# Voltage-Monitor.net
KiCad netlist of a schematic drawn in Altium Designer
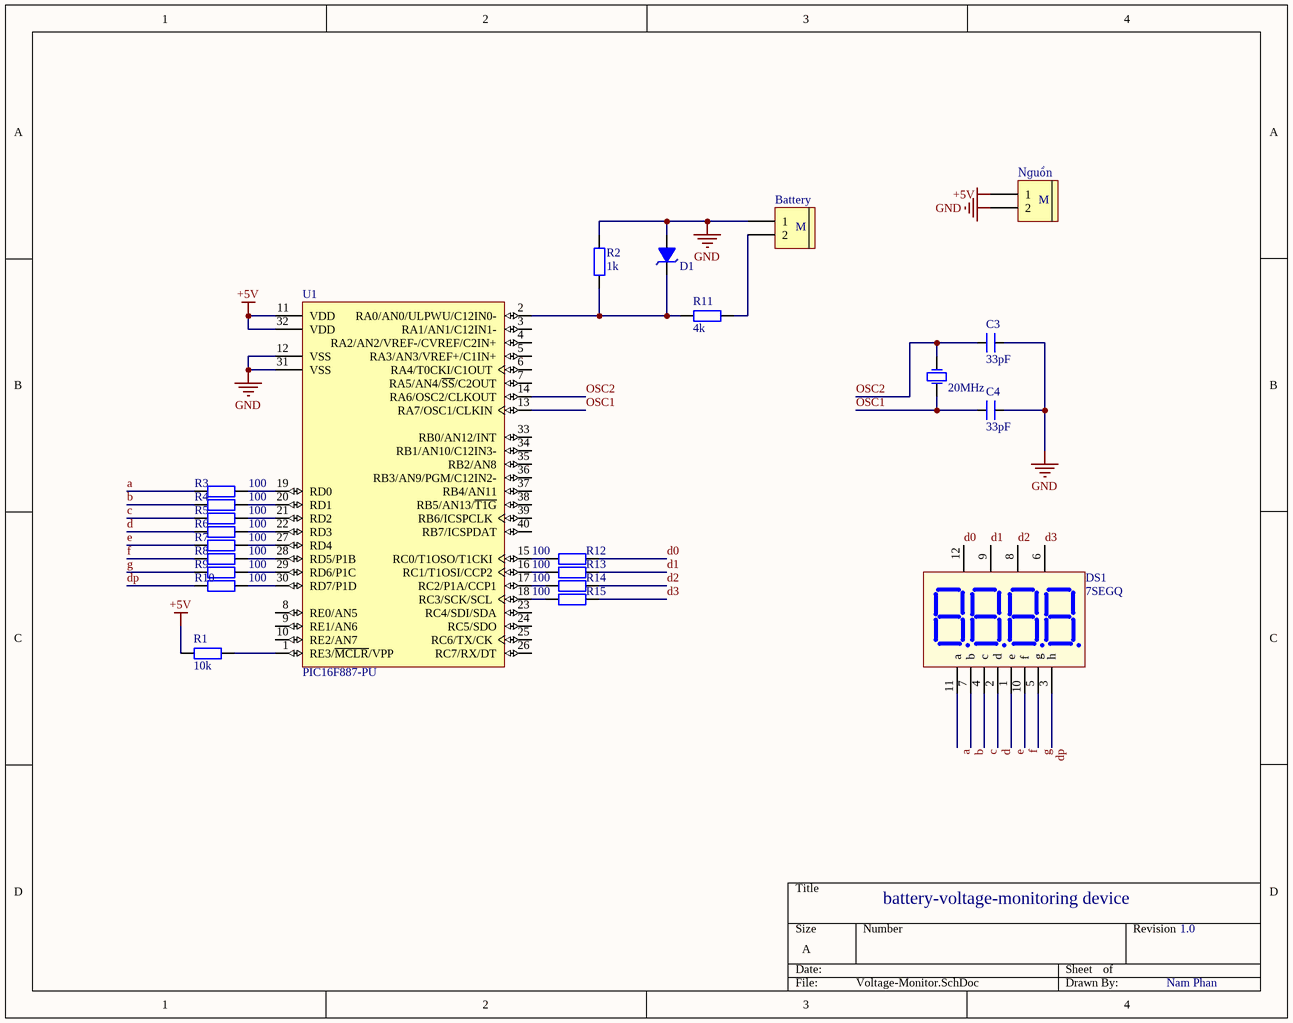
[diagram p0: Voltage-Monitor.SchDoc]

(export (version "E")
  (design (tool "Eeschema 10.0.6"))
  (components
    (comp (ref "Battery")
      (value "Header 2 - M")
      (footprint "Medium - Header 2")
      (description "Header, 2-Pin, Medium")
      (fields (field (name "PUBLISHER") "Altium Limited"))
      (libsource (lib "minhha") (part "Header 2 - M"))
    )
    (comp (ref "C3")
      (value "33pF")
      (footprint "CN1.5")
      (description "Cap np 682pF => 104pF")
      (libsource (lib "minhha") (part "CN1.5"))
    )
    (comp (ref "C4")
      (value "33pF")
      (footprint "CN1.5")
      (description "Cap np 682pF => 104pF")
      (libsource (lib "minhha") (part "CN1.5"))
    )
    (comp (ref "D1")
      (value "Diode Zener")
      (footprint "D1A")
      (description "Diode  Zener")
      (libsource (lib "minhha") (part "Diode Zener"))
    )
    (comp (ref "DS1")
      (value "7SEGQ")
      (footprint "LED7SEG-4-0.56")
      (description "Four 7 Seg Dipslay")
      (libsource (lib "Library1") (part "LED7SEG-4"))
    )
    (comp (ref "Nguồn")
      (value "Header 2 - M")
      (footprint "Medium - Header 2")
      (description "Header, 2-Pin, Medium")
      (fields (field (name "PUBLISHER") "Altium Limited"))
      (libsource (lib "minhha") (part "Header 2 - M"))
    )
    (comp (ref "R1")
      (value "10k")
      (footprint "R1/4W")
      (description "Resistor 1/4W")
      (libsource (lib "minhha") (part "R1/4W"))
    )
    (comp (ref "R2")
      (value "1k")
      (footprint "R1/4W")
      (description "Resistor 1/4W")
      (libsource (lib "minhha") (part "R1/4W"))
    )
    (comp (ref "R3")
      (value "100")
      (footprint "RESC-0603 (1608)")
      (description "RES SMD 5.6K OHM 1% 1/10W 0603")
      (fields (field (name "MPN") "RC0603FR-075K6L"))
      (libsource (lib "BYTECH_HW_LIB_2019 (1)") (part "RC0603FR-075K6L"))
    )
    (comp (ref "R4")
      (value "100")
      (footprint "RESC-0603 (1608)")
      (description "RES SMD 5.6K OHM 1% 1/10W 0603")
      (fields (field (name "MPN") "RC0603FR-075K6L"))
      (libsource (lib "BYTECH_HW_LIB_2019 (1)") (part "RC0603FR-075K6L"))
    )
    (comp (ref "R5")
      (value "100")
      (footprint "RESC-0603 (1608)")
      (description "RES SMD 5.6K OHM 1% 1/10W 0603")
      (fields (field (name "MPN") "RC0603FR-075K6L"))
      (libsource (lib "BYTECH_HW_LIB_2019 (1)") (part "RC0603FR-075K6L"))
    )
    (comp (ref "R6")
      (value "100")
      (footprint "RESC-0603 (1608)")
      (description "RES SMD 5.6K OHM 1% 1/10W 0603")
      (fields (field (name "MPN") "RC0603FR-075K6L"))
      (libsource (lib "BYTECH_HW_LIB_2019 (1)") (part "RC0603FR-075K6L"))
    )
    (comp (ref "R7")
      (value "100")
      (footprint "RESC-0603 (1608)")
      (description "RES SMD 5.6K OHM 1% 1/10W 0603")
      (fields (field (name "MPN") "RC0603FR-075K6L"))
      (libsource (lib "BYTECH_HW_LIB_2019 (1)") (part "RC0603FR-075K6L"))
    )
    (comp (ref "R8")
      (value "100")
      (footprint "RESC-0603 (1608)")
      (description "RES SMD 5.6K OHM 1% 1/10W 0603")
      (fields (field (name "MPN") "RC0603FR-075K6L"))
      (libsource (lib "BYTECH_HW_LIB_2019 (1)") (part "RC0603FR-075K6L"))
    )
    (comp (ref "R9")
      (value "100")
      (footprint "RESC-0603 (1608)")
      (description "RES SMD 5.6K OHM 1% 1/10W 0603")
      (fields (field (name "MPN") "RC0603FR-075K6L"))
      (libsource (lib "BYTECH_HW_LIB_2019 (1)") (part "RC0603FR-075K6L"))
    )
    (comp (ref "R10")
      (value "100")
      (footprint "RESC-0603 (1608)")
      (description "RES SMD 5.6K OHM 1% 1/10W 0603")
      (fields (field (name "MPN") "RC0603FR-075K6L"))
      (libsource (lib "BYTECH_HW_LIB_2019 (1)") (part "RC0603FR-075K6L"))
    )
    (comp (ref "R11")
      (value "4k")
      (footprint "R1/4W")
      (description "Resistor 1/4W")
      (libsource (lib "minhha") (part "R1/4W"))
    )
    (comp (ref "R12")
      (value "100")
      (footprint "RESC-0603 (1608)")
      (description "RES SMD 5.6K OHM 1% 1/10W 0603")
      (fields (field (name "MPN") "RC0603FR-075K6L"))
      (libsource (lib "BYTECH_HW_LIB_2019 (1)") (part "RC0603FR-075K6L"))
    )
    (comp (ref "R13")
      (value "100")
      (footprint "RESC-0603 (1608)")
      (description "RES SMD 5.6K OHM 1% 1/10W 0603")
      (fields (field (name "MPN") "RC0603FR-075K6L"))
      (libsource (lib "BYTECH_HW_LIB_2019 (1)") (part "RC0603FR-075K6L"))
    )
    (comp (ref "R14")
      (value "100")
      (footprint "RESC-0603 (1608)")
      (description "RES SMD 5.6K OHM 1% 1/10W 0603")
      (fields (field (name "MPN") "RC0603FR-075K6L"))
      (libsource (lib "BYTECH_HW_LIB_2019 (1)") (part "RC0603FR-075K6L"))
    )
    (comp (ref "R15")
      (value "100")
      (footprint "RESC-0603 (1608)")
      (description "RES SMD 5.6K OHM 1% 1/10W 0603")
      (fields (field (name "MPN") "RC0603FR-075K6L"))
      (libsource (lib "BYTECH_HW_LIB_2019 (1)") (part "RC0603FR-075K6L"))
    )
    (comp (ref "U1")
      (value "PIC16F887-PU")
      (footprint "DIP40/W0.6")
      (fields (field (name "PUBLISHER") "Altium Limited"))
      (libsource (lib "Library1") (part "PIC16F887-PU"))
    )
    (comp (ref "Y1")
      (value "20MHz")
      (footprint "XT2")
      (description "Crystal Oscillator")
      (fields (field (name "PUBLISHER") "Altium Limited"))
      (libsource (lib "minhha") (part "Crystal"))
    )
  )
  (nets
    (net (code "1") (name "+5V") (class "Default")
      (node (ref "Nguồn") (pin "1") (pinfunction "1_1") (pintype "passive"))
      (node (ref "R1") (pin "1") (pinfunction "1_1") (pintype "passive"))
      (node (ref "U1") (pin "11") (pinfunction "VDD_11") (pintype "power_in"))
      (node (ref "U1") (pin "32") (pinfunction "VDD_32") (pintype "power_in"))
    )
    (net (code "2") (name "/OSC1") (class "Default")
      (node (ref "C4") (pin "1") (pinfunction "1_1") (pintype "passive"))
      (node (ref "U1") (pin "13") (pinfunction "RA7/OSC1/CLKIN_13") (pintype "bidirectional"))
      (node (ref "Y1") (pin "1") (pinfunction "OSC1_1") (pintype "passive"))
    )
    (net (code "3") (name "/OSC2") (class "Default")
      (node (ref "C3") (pin "1") (pinfunction "1_1") (pintype "passive"))
      (node (ref "U1") (pin "14") (pinfunction "RA6/OSC2/CLKOUT_14") (pintype "bidirectional"))
      (node (ref "Y1") (pin "2") (pinfunction "OSC2_2") (pintype "passive"))
    )
    (net (code "4") (name "/a") (class "Default")
      (node (ref "DS1") (pin "11") (pinfunction "a_11") (pintype "passive"))
      (node (ref "R3") (pin "1") (pinfunction "1_1") (pintype "passive"))
    )
    (net (code "5") (name "/b") (class "Default")
      (node (ref "DS1") (pin "7") (pinfunction "b_7") (pintype "passive"))
      (node (ref "R4") (pin "1") (pinfunction "1_1") (pintype "passive"))
    )
    (net (code "6") (name "/c") (class "Default")
      (node (ref "DS1") (pin "4") (pinfunction "c_4") (pintype "passive"))
      (node (ref "R5") (pin "1") (pinfunction "1_1") (pintype "passive"))
    )
    (net (code "7") (name "/d") (class "Default")
      (node (ref "DS1") (pin "2") (pinfunction "d_2") (pintype "passive"))
      (node (ref "R6") (pin "1") (pinfunction "1_1") (pintype "passive"))
    )
    (net (code "8") (name "/d0") (class "Default")
      (node (ref "DS1") (pin "12") (pinfunction "V1_12") (pintype "passive"))
      (node (ref "R12") (pin "2") (pinfunction "2_2") (pintype "passive"))
    )
    (net (code "9") (name "/d1") (class "Default")
      (node (ref "DS1") (pin "9") (pinfunction "V2_9") (pintype "passive"))
      (node (ref "R13") (pin "2") (pinfunction "2_2") (pintype "passive"))
    )
    (net (code "10") (name "/d2") (class "Default")
      (node (ref "DS1") (pin "8") (pinfunction "V3_8") (pintype "passive"))
      (node (ref "R14") (pin "2") (pinfunction "2_2") (pintype "passive"))
    )
    (net (code "11") (name "/d3") (class "Default")
      (node (ref "DS1") (pin "6") (pinfunction "V4_6") (pintype "passive"))
      (node (ref "R15") (pin "2") (pinfunction "2_2") (pintype "passive"))
    )
    (net (code "12") (name "/dp") (class "Default")
      (node (ref "DS1") (pin "3") (pinfunction "h_3") (pintype "passive"))
      (node (ref "R10") (pin "1") (pinfunction "1_1") (pintype "passive"))
    )
    (net (code "13") (name "/e") (class "Default")
      (node (ref "DS1") (pin "1") (pinfunction "e_1") (pintype "passive"))
      (node (ref "R7") (pin "1") (pinfunction "1_1") (pintype "passive"))
    )
    (net (code "14") (name "/f") (class "Default")
      (node (ref "DS1") (pin "10") (pinfunction "f_10") (pintype "passive"))
      (node (ref "R8") (pin "1") (pinfunction "1_1") (pintype "passive"))
    )
    (net (code "15") (name "/g") (class "Default")
      (node (ref "DS1") (pin "5") (pinfunction "g_5") (pintype "passive"))
      (node (ref "R9") (pin "1") (pinfunction "1_1") (pintype "passive"))
    )
    (net (code "16") (name "GND") (class "Default")
      (node (ref "Battery") (pin "1") (pinfunction "1_1") (pintype "passive"))
      (node (ref "C3") (pin "2") (pinfunction "2_2") (pintype "passive"))
      (node (ref "C4") (pin "2") (pinfunction "2_2") (pintype "passive"))
      (node (ref "D1") (pin "1") (pinfunction "A_1") (pintype "passive"))
      (node (ref "Nguồn") (pin "2") (pinfunction "2_2") (pintype "passive"))
      (node (ref "R2") (pin "2") (pinfunction "2_2") (pintype "passive"))
      (node (ref "U1") (pin "12") (pinfunction "VSS_12") (pintype "power_in"))
      (node (ref "U1") (pin "31") (pinfunction "VSS_31") (pintype "power_in"))
    )
    (net (code "17") (name "Net-(Battery-Pad2)") (class "Default")
      (node (ref "Battery") (pin "2") (pinfunction "2_2") (pintype "passive"))
      (node (ref "R11") (pin "2") (pinfunction "2_2") (pintype "passive"))
    )
    (net (code "18") (name "Net-(D1-K)") (class "Default")
      (node (ref "D1") (pin "2") (pinfunction "K_2") (pintype "passive"))
      (node (ref "R11") (pin "1") (pinfunction "1_1") (pintype "passive"))
      (node (ref "R2") (pin "1") (pinfunction "1_1") (pintype "passive"))
      (node (ref "U1") (pin "2") (pinfunction "RA0/AN0/ULPWU/C12IN0-_2") (pintype "bidirectional"))
    )
    (net (code "19") (name "Net-(U1-RC0{slash}T1OSO{slash}T1CKI)") (class "Default")
      (node (ref "R12") (pin "1") (pinfunction "1_1") (pintype "passive"))
      (node (ref "U1") (pin "15") (pinfunction "RC0/T1OSO/T1CKI_15") (pintype "bidirectional"))
    )
    (net (code "20") (name "Net-(U1-RC1{slash}T1OSI{slash}CCP2)") (class "Default")
      (node (ref "R13") (pin "1") (pinfunction "1_1") (pintype "passive"))
      (node (ref "U1") (pin "16") (pinfunction "RC1/T1OSI/CCP2_16") (pintype "bidirectional"))
    )
    (net (code "21") (name "Net-(U1-RC2{slash}P1A{slash}CCP1)") (class "Default")
      (node (ref "R14") (pin "1") (pinfunction "1_1") (pintype "passive"))
      (node (ref "U1") (pin "17") (pinfunction "RC2/P1A/CCP1_17") (pintype "bidirectional"))
    )
    (net (code "22") (name "Net-(U1-RC3{slash}SCK{slash}SCL)") (class "Default")
      (node (ref "R15") (pin "1") (pinfunction "1_1") (pintype "passive"))
      (node (ref "U1") (pin "18") (pinfunction "RC3/SCK/SCL_18") (pintype "bidirectional"))
    )
    (net (code "23") (name "Net-(U1-RD0)") (class "Default")
      (node (ref "R3") (pin "2") (pinfunction "2_2") (pintype "passive"))
      (node (ref "U1") (pin "19") (pinfunction "RD0_19") (pintype "bidirectional"))
    )
    (net (code "24") (name "Net-(U1-RD1)") (class "Default")
      (node (ref "R4") (pin "2") (pinfunction "2_2") (pintype "passive"))
      (node (ref "U1") (pin "20") (pinfunction "RD1_20") (pintype "bidirectional"))
    )
    (net (code "25") (name "Net-(U1-RD2)") (class "Default")
      (node (ref "R5") (pin "2") (pinfunction "2_2") (pintype "passive"))
      (node (ref "U1") (pin "21") (pinfunction "RD2_21") (pintype "bidirectional"))
    )
    (net (code "26") (name "Net-(U1-RD3)") (class "Default")
      (node (ref "R6") (pin "2") (pinfunction "2_2") (pintype "passive"))
      (node (ref "U1") (pin "22") (pinfunction "RD3_22") (pintype "bidirectional"))
    )
    (net (code "27") (name "Net-(U1-RD4)") (class "Default")
      (node (ref "R7") (pin "2") (pinfunction "2_2") (pintype "passive"))
      (node (ref "U1") (pin "27") (pinfunction "RD4_27") (pintype "bidirectional"))
    )
    (net (code "28") (name "Net-(U1-RD5{slash}P1B)") (class "Default")
      (node (ref "R8") (pin "2") (pinfunction "2_2") (pintype "passive"))
      (node (ref "U1") (pin "28") (pinfunction "RD5/P1B_28") (pintype "bidirectional"))
    )
    (net (code "29") (name "Net-(U1-RD6{slash}P1C)") (class "Default")
      (node (ref "R9") (pin "2") (pinfunction "2_2") (pintype "passive"))
      (node (ref "U1") (pin "29") (pinfunction "RD6/P1C_29") (pintype "bidirectional"))
    )
    (net (code "30") (name "Net-(U1-RD7{slash}P1D)") (class "Default")
      (node (ref "R10") (pin "2") (pinfunction "2_2") (pintype "passive"))
      (node (ref "U1") (pin "30") (pinfunction "RD7/P1D_30") (pintype "bidirectional"))
    )
    (net (code "31") (name "Net-(U1-RE3{slash}~{MCLR}{slash}VPP)") (class "Default")
      (node (ref "R1") (pin "2") (pinfunction "2_2") (pintype "passive"))
      (node (ref "U1") (pin "1") (pinfunction "RE3/~{MCLR}/VPP_1") (pintype "bidirectional"))
    )
    (net (code "32") (name "unconnected-(U1-RA1{slash}AN1{slash}C12IN1--Pad3)") (class "Default")
      (node (ref "U1") (pin "3") (pinfunction "RA1/AN1/C12IN1-_3") (pintype "bidirectional"))
    )
    (net (code "33") (name "unconnected-(U1-RA2{slash}AN2{slash}VREF-{slash}CVREF{slash}C2IN+-Pad4)") (class "Default")
      (node (ref "U1") (pin "4") (pinfunction "RA2/AN2/VREF-/CVREF/C2IN+_4") (pintype "bidirectional"))
    )
    (net (code "34") (name "unconnected-(U1-RA3{slash}AN3{slash}VREF+{slash}C1IN+-Pad5)") (class "Default")
      (node (ref "U1") (pin "5") (pinfunction "RA3/AN3/VREF+/C1IN+_5") (pintype "bidirectional"))
    )
    (net (code "35") (name "unconnected-(U1-RA4{slash}T0CKI{slash}C1OUT-Pad6)") (class "Default")
      (node (ref "U1") (pin "6") (pinfunction "RA4/T0CKI/C1OUT_6") (pintype "bidirectional"))
    )
    (net (code "36") (name "unconnected-(U1-RA5{slash}AN4{slash}~{SS}{slash}C2OUT-Pad7)") (class "Default")
      (node (ref "U1") (pin "7") (pinfunction "RA5/AN4/~{SS}/C2OUT_7") (pintype "bidirectional"))
    )
    (net (code "37") (name "unconnected-(U1-RB0{slash}AN12{slash}INT-Pad33)") (class "Default")
      (node (ref "U1") (pin "33") (pinfunction "RB0/AN12/INT_33") (pintype "bidirectional"))
    )
    (net (code "38") (name "unconnected-(U1-RB1{slash}AN10{slash}C12IN3--Pad34)") (class "Default")
      (node (ref "U1") (pin "34") (pinfunction "RB1/AN10/C12IN3-_34") (pintype "bidirectional"))
    )
    (net (code "39") (name "unconnected-(U1-RB2{slash}AN8-Pad35)") (class "Default")
      (node (ref "U1") (pin "35") (pinfunction "RB2/AN8_35") (pintype "bidirectional"))
    )
    (net (code "40") (name "unconnected-(U1-RB3{slash}AN9{slash}PGM{slash}C12IN2--Pad36)") (class "Default")
      (node (ref "U1") (pin "36") (pinfunction "RB3/AN9/PGM/C12IN2-_36") (pintype "bidirectional"))
    )
    (net (code "41") (name "unconnected-(U1-RB4{slash}AN11-Pad37)") (class "Default")
      (node (ref "U1") (pin "37") (pinfunction "RB4/AN11_37") (pintype "bidirectional"))
    )
    (net (code "42") (name "unconnected-(U1-RB5{slash}AN13{slash}~{T1G}-Pad38)") (class "Default")
      (node (ref "U1") (pin "38") (pinfunction "RB5/AN13/~{T1G}_38") (pintype "bidirectional"))
    )
    (net (code "43") (name "unconnected-(U1-RB6{slash}ICSPCLK-Pad39)") (class "Default")
      (node (ref "U1") (pin "39") (pinfunction "RB6/ICSPCLK_39") (pintype "bidirectional"))
    )
    (net (code "44") (name "unconnected-(U1-RB7{slash}ICSPDAT-Pad40)") (class "Default")
      (node (ref "U1") (pin "40") (pinfunction "RB7/ICSPDAT_40") (pintype "bidirectional"))
    )
    (net (code "45") (name "unconnected-(U1-RC4{slash}SDI{slash}SDA-Pad23)") (class "Default")
      (node (ref "U1") (pin "23") (pinfunction "RC4/SDI/SDA_23") (pintype "bidirectional"))
    )
    (net (code "46") (name "unconnected-(U1-RC5{slash}SDO-Pad24)") (class "Default")
      (node (ref "U1") (pin "24") (pinfunction "RC5/SDO_24") (pintype "bidirectional"))
    )
    (net (code "47") (name "unconnected-(U1-RC6{slash}TX{slash}CK-Pad25)") (class "Default")
      (node (ref "U1") (pin "25") (pinfunction "RC6/TX/CK_25") (pintype "bidirectional"))
    )
    (net (code "48") (name "unconnected-(U1-RC7{slash}RX{slash}DT-Pad26)") (class "Default")
      (node (ref "U1") (pin "26") (pinfunction "RC7/RX/DT_26") (pintype "bidirectional"))
    )
    (net (code "49") (name "unconnected-(U1-RE0{slash}AN5-Pad8)") (class "Default")
      (node (ref "U1") (pin "8") (pinfunction "RE0/AN5_8") (pintype "bidirectional"))
    )
    (net (code "50") (name "unconnected-(U1-RE1{slash}AN6-Pad9)") (class "Default")
      (node (ref "U1") (pin "9") (pinfunction "RE1/AN6_9") (pintype "bidirectional"))
    )
    (net (code "51") (name "unconnected-(U1-RE2{slash}AN7-Pad10)") (class "Default")
      (node (ref "U1") (pin "10") (pinfunction "RE2/AN7_10") (pintype "bidirectional"))
    )
  )
)
